# mini_optronV3.net
KiCad netlist of a schematic drawn in EAGLE
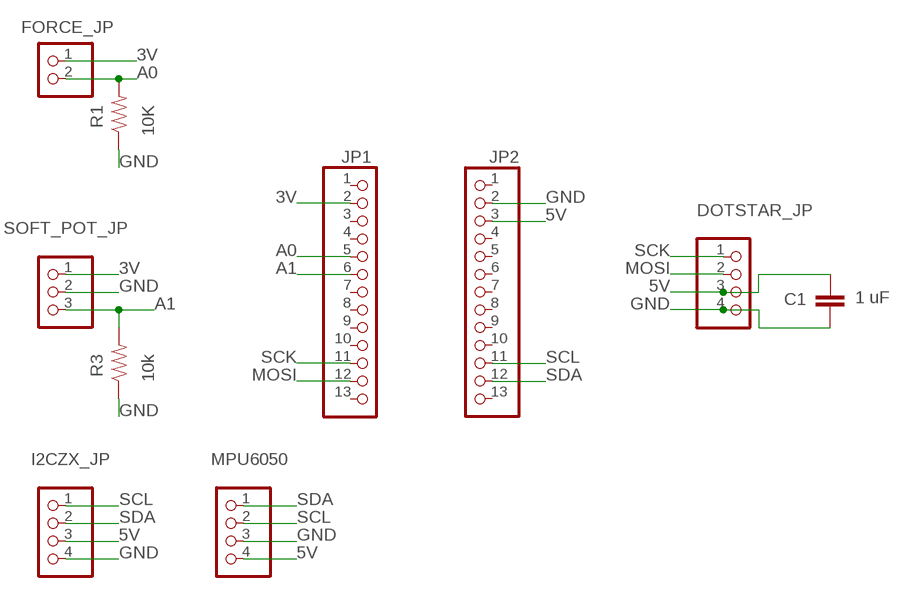
[diagram p0: schematic, sheet 1]

(export (version "E")
  (design (tool "Eeschema 10.0.6"))
  (components
    (comp (ref "C1")
      (value "1 uF")
      (footprint "eagle-import:C5B7.2")
      (fields (field (name "MF") "AVX") (field (name "MPN") "0805YD105KAT2A"))
      (libsource (lib "eagle-import") (part "C5/7.2"))
    )
    (comp (ref "DOTSTAR_JP")
      (value "PINHD-1X4")
      (footprint "eagle-import:1X04")
      (libsource (lib "eagle-import") (part "PINHD-1X4"))
    )
    (comp (ref "FORCE_JP")
      (value "PINHD-1X2")
      (footprint "eagle-import:1X02")
      (libsource (lib "eagle-import") (part "PINHD-1X2"))
    )
    (comp (ref "I2CZX_JP")
      (value "PINHD-1X4")
      (footprint "eagle-import:1X04")
      (libsource (lib "eagle-import") (part "PINHD-1X4"))
    )
    (comp (ref "JP1")
      (value "PINHD-1X13_BIG")
      (footprint "eagle-import:1X13-BIG")
      (libsource (lib "eagle-import") (part "PINHD-1X13_BIG"))
    )
    (comp (ref "JP2")
      (value "PINHD-1X13_BIG")
      (footprint "eagle-import:1X13-BIG")
      (libsource (lib "eagle-import") (part "PINHD-1X13_BIG"))
    )
    (comp (ref "MPU6050")
      (value "PINHD-1X4")
      (footprint "eagle-import:1X04")
      (libsource (lib "eagle-import") (part "PINHD-1X4"))
    )
    (comp (ref "R1")
      (value "10K")
      (footprint "eagle-import:AXIAL-0.3")
      (fields (field (name "MF") "VISHAY") (field (name "MPN") "CRCW060310K0FKEA"))
      (libsource (lib "eagle-import") (part "RESISTORAXIAL-0.3"))
    )
    (comp (ref "R3")
      (value "10k")
      (footprint "eagle-import:AXIAL-0.3")
      (fields (field (name "MF") "VISHAY") (field (name "MPN") "CRCW060310K0FKEA"))
      (libsource (lib "eagle-import") (part "RESISTORAXIAL-0.3"))
    )
    (comp (ref "SOFT_POT_JP")
      (value "PINHD-1X3")
      (footprint "eagle-import:1X03")
      (libsource (lib "eagle-import") (part "PINHD-1X3"))
    )
  )
  (nets
    (net (code "1") (name "/3V") (class "Default")
      (node (ref "FORCE_JP") (pin "1") (pinfunction "1_1") (pintype "passive"))
      (node (ref "JP1") (pin "2") (pinfunction "2_2") (pintype "passive"))
      (node (ref "SOFT_POT_JP") (pin "1") (pinfunction "1_1") (pintype "passive"))
    )
    (net (code "2") (name "/5V") (class "Default")
      (node (ref "C1") (pin "1") (pinfunction "1_1") (pintype "passive"))
      (node (ref "DOTSTAR_JP") (pin "3") (pinfunction "3_3") (pintype "passive"))
      (node (ref "I2CZX_JP") (pin "3") (pinfunction "3_3") (pintype "passive"))
      (node (ref "JP2") (pin "3") (pinfunction "3_3") (pintype "passive"))
      (node (ref "MPU6050") (pin "4") (pinfunction "4_4") (pintype "passive"))
    )
    (net (code "3") (name "/A0") (class "Default")
      (node (ref "FORCE_JP") (pin "2") (pinfunction "2_2") (pintype "passive"))
      (node (ref "JP1") (pin "5") (pinfunction "5_5") (pintype "passive"))
      (node (ref "R1") (pin "P$2") (pinfunction "2_P$2") (pintype "passive"))
    )
    (net (code "4") (name "/A1") (class "Default")
      (node (ref "JP1") (pin "6") (pinfunction "6_6") (pintype "passive"))
      (node (ref "R3") (pin "P$2") (pinfunction "2_P$2") (pintype "passive"))
      (node (ref "SOFT_POT_JP") (pin "3") (pinfunction "3_3") (pintype "passive"))
    )
    (net (code "5") (name "/GND") (class "Default")
      (node (ref "C1") (pin "2") (pinfunction "2_2") (pintype "passive"))
      (node (ref "DOTSTAR_JP") (pin "4") (pinfunction "4_4") (pintype "passive"))
      (node (ref "I2CZX_JP") (pin "4") (pinfunction "4_4") (pintype "passive"))
      (node (ref "JP2") (pin "2") (pinfunction "2_2") (pintype "passive"))
      (node (ref "MPU6050") (pin "3") (pinfunction "3_3") (pintype "passive"))
      (node (ref "R1") (pin "P$1") (pinfunction "1_P$1") (pintype "passive"))
      (node (ref "R3") (pin "P$1") (pinfunction "1_P$1") (pintype "passive"))
      (node (ref "SOFT_POT_JP") (pin "2") (pinfunction "2_2") (pintype "passive"))
    )
    (net (code "6") (name "/MOSI") (class "Default")
      (node (ref "DOTSTAR_JP") (pin "2") (pinfunction "2_2") (pintype "passive"))
      (node (ref "JP1") (pin "12") (pinfunction "12_12") (pintype "passive"))
    )
    (net (code "7") (name "/SCK") (class "Default")
      (node (ref "DOTSTAR_JP") (pin "1") (pinfunction "1_1") (pintype "passive"))
      (node (ref "JP1") (pin "11") (pinfunction "11_11") (pintype "passive"))
    )
    (net (code "8") (name "/SCL") (class "Default")
      (node (ref "I2CZX_JP") (pin "1") (pinfunction "1_1") (pintype "passive"))
      (node (ref "JP2") (pin "11") (pinfunction "11_11") (pintype "passive"))
      (node (ref "MPU6050") (pin "2") (pinfunction "2_2") (pintype "passive"))
    )
    (net (code "9") (name "/SDA") (class "Default")
      (node (ref "I2CZX_JP") (pin "2") (pinfunction "2_2") (pintype "passive"))
      (node (ref "JP2") (pin "12") (pinfunction "12_12") (pintype "passive"))
      (node (ref "MPU6050") (pin "1") (pinfunction "1_1") (pintype "passive"))
    )
    (net (code "10") (name "unconnected-(JP1-Pad1)") (class "Default")
      (node (ref "JP1") (pin "1") (pinfunction "1_1") (pintype "passive"))
    )
    (net (code "11") (name "unconnected-(JP1-Pad3)") (class "Default")
      (node (ref "JP1") (pin "3") (pinfunction "3_3") (pintype "passive"))
    )
    (net (code "12") (name "unconnected-(JP1-Pad4)") (class "Default")
      (node (ref "JP1") (pin "4") (pinfunction "4_4") (pintype "passive"))
    )
    (net (code "13") (name "unconnected-(JP1-Pad7)") (class "Default")
      (node (ref "JP1") (pin "7") (pinfunction "7_7") (pintype "passive"))
    )
    (net (code "14") (name "unconnected-(JP1-Pad8)") (class "Default")
      (node (ref "JP1") (pin "8") (pinfunction "8_8") (pintype "passive"))
    )
    (net (code "15") (name "unconnected-(JP1-Pad9)") (class "Default")
      (node (ref "JP1") (pin "9") (pinfunction "9_9") (pintype "passive"))
    )
    (net (code "16") (name "unconnected-(JP1-Pad10)") (class "Default")
      (node (ref "JP1") (pin "10") (pinfunction "10_10") (pintype "passive"))
    )
    (net (code "17") (name "unconnected-(JP1-Pad13)") (class "Default")
      (node (ref "JP1") (pin "13") (pinfunction "13_13") (pintype "passive"))
    )
    (net (code "18") (name "unconnected-(JP2-Pad1)") (class "Default")
      (node (ref "JP2") (pin "1") (pinfunction "1_1") (pintype "passive"))
    )
    (net (code "19") (name "unconnected-(JP2-Pad4)") (class "Default")
      (node (ref "JP2") (pin "4") (pinfunction "4_4") (pintype "passive"))
    )
    (net (code "20") (name "unconnected-(JP2-Pad5)") (class "Default")
      (node (ref "JP2") (pin "5") (pinfunction "5_5") (pintype "passive"))
    )
    (net (code "21") (name "unconnected-(JP2-Pad6)") (class "Default")
      (node (ref "JP2") (pin "6") (pinfunction "6_6") (pintype "passive"))
    )
    (net (code "22") (name "unconnected-(JP2-Pad7)") (class "Default")
      (node (ref "JP2") (pin "7") (pinfunction "7_7") (pintype "passive"))
    )
    (net (code "23") (name "unconnected-(JP2-Pad8)") (class "Default")
      (node (ref "JP2") (pin "8") (pinfunction "8_8") (pintype "passive"))
    )
    (net (code "24") (name "unconnected-(JP2-Pad9)") (class "Default")
      (node (ref "JP2") (pin "9") (pinfunction "9_9") (pintype "passive"))
    )
    (net (code "25") (name "unconnected-(JP2-Pad10)") (class "Default")
      (node (ref "JP2") (pin "10") (pinfunction "10_10") (pintype "passive"))
    )
    (net (code "26") (name "unconnected-(JP2-Pad13)") (class "Default")
      (node (ref "JP2") (pin "13") (pinfunction "13_13") (pintype "passive"))
    )
  )
)
